# DIG_PDU.net
KiCad netlist of a schematic drawn in Altium Designer
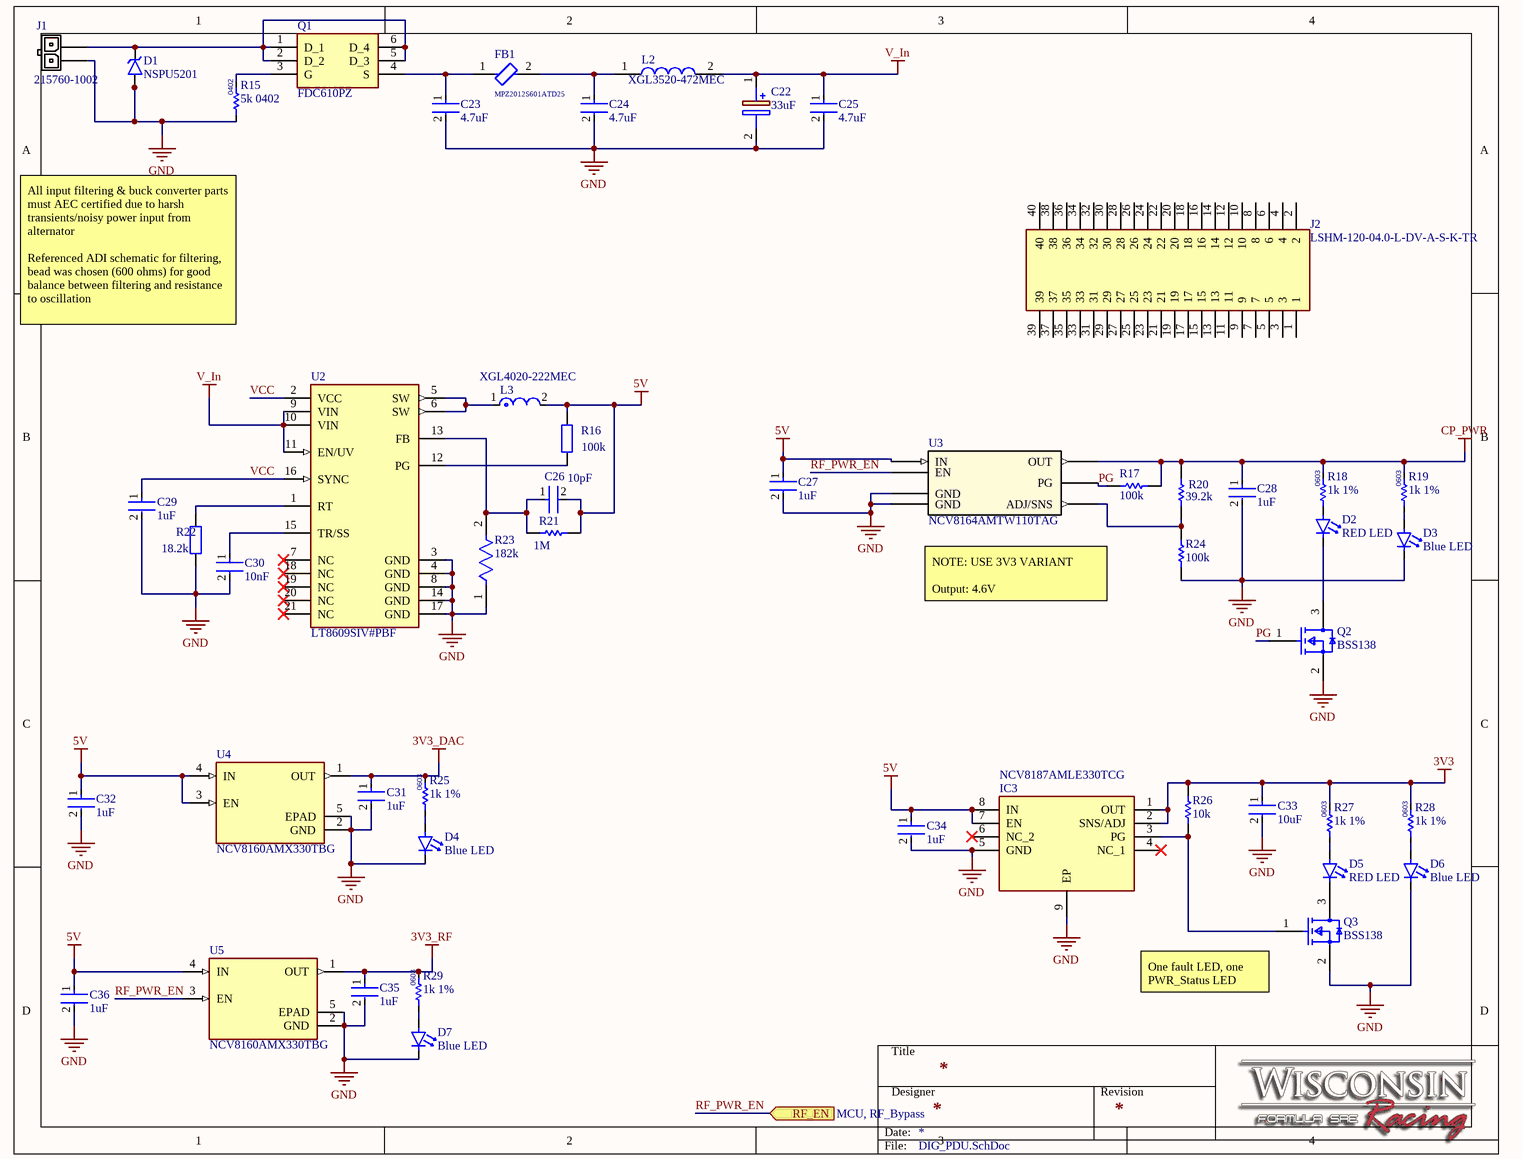
[diagram p0: DIG_PDU.SchDoc]

(export (version "E")
  (design (tool "Eeschema 10.0.6"))
  (components
    (comp (ref "C22")
      (value "33uF")
      (footprint "SamacSys:MAL215097904E3")
      (description "Capacitor Polarised\r\n\r\nMAL215097904E3")
      (fields
        (field (name "MANUFACTURER_PART_NUMBER") "MAL215097904E3")
        (field (name "MOUSER PART NUMBER") "594-MAL215097904E3")
      )
      (libsource (lib "*") (part "MAL215097904E3"))
    )
    (comp (ref "C23")
      (value "4.7uF")
      (footprint "FP-CGA4J-IPC_C")
      (description "Cap Ceramic 4.7uF 50V X7R 10% Pad SMD 0805 +125°C Automotive T/R")
      (libsource (lib "Altium Content Vault") (part "b4654b650e69147ec39a6b967a45e02"))
    )
    (comp (ref "C24")
      (value "4.7uF")
      (footprint "FP-CGA4J-IPC_C")
      (description "Cap Ceramic 4.7uF 50V X7R 10% Pad SMD 0805 +125°C Automotive T/R")
      (libsource (lib "Altium Content Vault") (part "b4654b650e69147ec39a6b967a45e02"))
    )
    (comp (ref "C25")
      (value "4.7uF")
      (footprint "FP-CGA4J-IPC_C")
      (description "Cap Ceramic 4.7uF 50V X7R 10% Pad SMD 0805 +125°C Automotive T/R")
      (libsource (lib "Altium Content Vault") (part "b4654b650e69147ec39a6b967a45e02"))
    )
    (comp (ref "C26")
      (value "10pF")
      (footprint "FP-GCM155-0_05-IPC_C")
      (description "Ceramic Capacitor for Automotive 10pF ±5% 50VDC C0G 0402 Paper T/R")
      (fields (field (name "TOLERANCE") "5%"))
      (libsource (lib "Altium Content Vault") (part "02cd4be3c70576c341d710602a673aa"))
    )
    (comp (ref "C27")
      (value "1uF")
      (footprint "FP-GRM155-0_1-IPC_C")
      (libsource (lib "Altium Content Vault") (part "11868f565c42a9108669ba33697ecf6"))
    )
    (comp (ref "C28")
      (value "1uF")
      (footprint "FP-GRM155-0_1-IPC_C")
      (libsource (lib "Altium Content Vault") (part "11868f565c42a9108669ba33697ecf6"))
    )
    (comp (ref "C29")
      (value "1uF")
      (footprint "FP-GRT155-0_1-IPC_A")
      (description "Multi-Layer Ceramic Capacitor 1uF 25V X6S ±10% 0402 Paper T/R\r\n\r\nGRT155C81E105KE13D")
      (libsource (lib "Altium Content Vault") (part "02cd4be3c70576c341d710602a673aa"))
    )
    (comp (ref "C30")
      (value "10nF")
      (footprint "FP-GCM155-0_05-IPC_C")
      (description "Ceramic Capacitor for Automotive 10nF ±10% 50VDC X7R 0402 Paper T/R\r\n\r\nGCM155R71H103KA55D")
      (fields (field (name "TOLERANCE") "10%") (field (name "VOLTAGE") "50V"))
      (libsource (lib "Altium Content Vault") (part "02cd4be3c70576c341d710602a673aa"))
    )
    (comp (ref "C31")
      (value "1uF")
      (footprint "FP-GRM155-0_1-IPC_C")
      (libsource (lib "Altium Content Vault") (part "11868f565c42a9108669ba33697ecf6"))
    )
    (comp (ref "C32")
      (value "1uF")
      (footprint "FP-GRM155-0_1-IPC_C")
      (libsource (lib "Altium Content Vault") (part "11868f565c42a9108669ba33697ecf6"))
    )
    (comp (ref "C33")
      (value "10uF")
      (footprint "FP-GRM155-0_2-IPC_A")
      (description "Chip Multilayer Ceramic Capacitors for General Purpose, 0402, 10uF, X5R, 15%, 20%, 6.3V")
      (libsource (lib "Altium Content Vault") (part "b4654b650e69147ec39a6b967a45e02"))
    )
    (comp (ref "C34")
      (value "1uF")
      (footprint "FP-GRM155-0_1-IPC_C")
      (libsource (lib "Altium Content Vault") (part "11868f565c42a9108669ba33697ecf6"))
    )
    (comp (ref "C35")
      (value "1uF")
      (footprint "FP-GRM155-0_1-IPC_C")
      (libsource (lib "Altium Content Vault") (part "11868f565c42a9108669ba33697ecf6"))
    )
    (comp (ref "C36")
      (value "1uF")
      (footprint "FP-GRM155-0_1-IPC_C")
      (libsource (lib "Altium Content Vault") (part "11868f565c42a9108669ba33697ecf6"))
    )
    (comp (ref "D1")
      (value "NSPU5201")
      (footprint "NSPM5131MUTBG")
      (fields
        (field (name "ARROW PART NUMBER") "NSPU5201MUTBG")
        (field (name "MOUSER PART NUMBER") "863-NSPU5201MUTBG")
      )
      (libsource (lib "University of Wisconsin Formula FSAE") (part "NSPU5201MUTBG"))
    )
    (comp (ref "D2")
      (value "RED LED")
      (footprint "DIOC1608X05N")
      (description "0603 Red SMD Led")
      (libsource (lib "University of Wisconsin Formula FSAE") (part "L196L-LIC-Symbol-1"))
    )
    (comp (ref "D3")
      (value "Blue LED")
      (footprint "0603-LED-1")
      (description "Single Color LED, Blue, Water Clear, 1.1mm")
      (libsource (lib "University of Wisconsin Formula FSAE") (part "LED"))
    )
    (comp (ref "D4")
      (value "Blue LED")
      (footprint "0603-LED-1")
      (description "Single Color LED, Blue, Water Clear, 1.1mm")
      (libsource (lib "University of Wisconsin Formula FSAE") (part "LED"))
    )
    (comp (ref "D5")
      (value "RED LED")
      (footprint "DIOC1608X05N")
      (description "0603 Red SMD Led")
      (libsource (lib "University of Wisconsin Formula FSAE") (part "L196L-LIC-Symbol-1"))
    )
    (comp (ref "D6")
      (value "Blue LED")
      (footprint "0603-LED-1")
      (description "Single Color LED, Blue, Water Clear, 1.1mm")
      (libsource (lib "University of Wisconsin Formula FSAE") (part "LED"))
    )
    (comp (ref "D7")
      (value "Blue LED")
      (footprint "0603-LED-1")
      (description "Single Color LED, Blue, Water Clear, 1.1mm")
      (libsource (lib "University of Wisconsin Formula FSAE") (part "LED"))
    )
    (comp (ref "FB1")
      (value "MPZ2012S601ATD25")
      (footprint "BEADC2012X105N")
      (description "Ferrite Beads Multi-Layer Power 600Ohm 25% 100MHz 2A 100mOhm DCR 0805 Automotive T/R")
      (fields (field (name "MOUSER PART NUMBER") "810-MPZ2012S601ATD25"))
      (libsource (lib "University of Wisconsin Formula FSAE") (part "MPZ2012S601ATD25"))
    )
    (comp (ref "IC3")
      (value "NCV8187AMLE330TCG")
      (footprint "SamacSys:SON65P300X300X100-9N-D")
      (description "Integrated Circuit")
      (fields (field (name "MOUSER PART NUMBER") "863-CV8187AMLE330TCG"))
      (libsource (lib "*") (part "NCV8187AMLE330TCG"))
    )
    (comp (ref "J1")
      (value "215760-1002")
      (footprint "215760-1002-Footprint-1")
      (libsource (lib "University of Wisconsin Formula FSAE") (part "961102-6404-AR"))
    )
    (comp (ref "J2")
      (value "LSHM-120-04.0-L-DV-A-S-K-TR")
      (footprint "SamacSys:LSHM-120-XX.X-YYY-DV-A-S-K-TR")
      (description "Connector")
      (fields (field (name "MOUSER PART NUMBER") "200-LSHM12004LDVASK"))
      (libsource (lib "*") (part "LSHM-120-04.0-L-DV-A-S-K-TR"))
    )
    (comp (ref "L2")
      (value "XGL3520-472MEC")
      (footprint "SamacSys:XGL3520472MEC")
      (description "Inductor")
      (libsource (lib "*") (part "XGL3520-472MEC"))
    )
    (comp (ref "L3")
      (value "XGL4020-222MEC")
      (footprint "FP-XGL4020-MFG")
      (description "Shielded Power Inductors")
      (libsource (lib "Altium Content Vault") (part "4cc4b267dca4c8e51f7102f422741d8"))
    )
    (comp (ref "Q1")
      (value "FDC610PZ")
      (footprint "SamacSys:SOT95P280X110-6N")
      (description "MOSFET (P-Channel)")
      (fields (field (name "MOUSER PART NUMBER") "512-FDC610PZ"))
      (libsource (lib "*") (part "FDC610PZ"))
    )
    (comp (ref "Q2")
      (value "BSS138")
      (footprint "FP-318-08-IPC_B")
      (description "MOSFET N-CH 50V 220MA SOT-23")
      (libsource (lib "Altium Content Vault") (part "3b9c635fedb024a5347a57b145af9cc"))
    )
    (comp (ref "Q3")
      (value "BSS138")
      (footprint "FP-318-08-IPC_B")
      (description "MOSFET N-CH 50V 220MA SOT-23")
      (libsource (lib "Altium Content Vault") (part "3b9c635fedb024a5347a57b145af9cc"))
    )
    (comp (ref "R15")
      (value "5k 0402")
      (footprint "Res0402-Type-1")
      (fields (field (name "TOLERANCE") "1%") (field (name "POWER") "63mW"))
      (libsource (lib "University of Wisconsin Formula FSAE") (part "RES"))
    )
    (comp (ref "R16")
      (value "100k")
      (footprint "WRIS-RSKS_0402")
      (description "Resistor, 100K, 0.1W, Thick Film, 0402 Rohs Compliant: Yes")
      (libsource (lib "Altium Content Vault") (part "Resistor"))
    )
    (comp (ref "R17")
      (value "100k")
      (footprint "RESC1005X40X25NL05T10")
      (fields (field (name "PART NUMBER") "RC0402FR-07100KL") (field (name "MANUFACTURER") "Yageo / Phycomp"))
      (libsource (lib "Altium Content Vault") (part "RES"))
    )
    (comp (ref "R18")
      (value "1k 1%")
      (footprint "Res0603-type-1")
      (libsource (lib "University of Wisconsin Formula FSAE") (part "RES 0603"))
    )
    (comp (ref "R19")
      (value "1k 1%")
      (footprint "Res0603-type-1")
      (libsource (lib "University of Wisconsin Formula FSAE") (part "RES 0603"))
    )
    (comp (ref "R20")
      (value "39.2k")
      (footprint "RESC1005X40X25ML05T10")
      (fields (field (name "PART NUMBER") "RC0402FR-0739K2L") (field (name "MANUFACTURER") "Yageo"))
      (libsource (lib "Altium Content Vault") (part "RES"))
    )
    (comp (ref "R21")
      (value "1M")
      (footprint "RESC1005X40X25NL05T10")
      (fields (field (name "MANUFACTURER") "Yageo / Phycomp") (field (name "PART NUMBER") "RC0402FR-071ML"))
      (libsource (lib "Altium Content Vault") (part "RES"))
    )
    (comp (ref "R22")
      (value "18.2k")
      (footprint "WRIS-RSKS_0402")
      (description "Resistor, 18K2, 0.1W, Thick Film, 0402 Rohs Compliant: Yes")
      (libsource (lib "Altium Content Vault") (part "Resistor"))
    )
    (comp (ref "R23")
      (value "182k")
      (footprint "FP-AC0402-IPC_C")
      (description "RES 182kΩ ±1% 0.063W 0402")
      (fields (field (name "TOLERANCE") "1%"))
      (libsource (lib "Altium Content Vault") (part "1029c3af85768c4190bb7ad29bc67b5"))
    )
    (comp (ref "R24")
      (value "100k")
      (footprint "RESC1005X40X25NL05T10")
      (fields (field (name "PART NUMBER") "RC0402FR-07100KL") (field (name "MANUFACTURER") "Yageo / Phycomp"))
      (libsource (lib "Altium Content Vault") (part "RES"))
    )
    (comp (ref "R25")
      (value "1k 1%")
      (footprint "Res0603-type-1")
      (libsource (lib "University of Wisconsin Formula FSAE") (part "RES 0603"))
    )
    (comp (ref "R26")
      (value "10k")
      (footprint "RESC1005X40X25ML05T05")
      (fields (field (name "PART NUMBER") "ERJ-2GEJ103X") (field (name "MANUFACTURER") "Panasonic"))
      (libsource (lib "Altium Content Vault") (part "RES"))
    )
    (comp (ref "R27")
      (value "1k 1%")
      (footprint "Res0603-type-1")
      (libsource (lib "University of Wisconsin Formula FSAE") (part "RES 0603"))
    )
    (comp (ref "R28")
      (value "1k 1%")
      (footprint "Res0603-type-1")
      (libsource (lib "University of Wisconsin Formula FSAE") (part "RES 0603"))
    )
    (comp (ref "R29")
      (value "1k 1%")
      (footprint "Res0603-type-1")
      (libsource (lib "University of Wisconsin Formula FSAE") (part "RES 0603"))
    )
    (comp (ref "U2")
      (value "LT8609SIV#PBF")
      (footprint "FP-LQFN-16-05-08-1516-MFG")
      (description "IC REG BUCK ADJUSTABLE 2A 16LQFN")
      (fields
        (field (name "OCTOPART") "https://octopart.com/lt8609siv%23pbf-analog+devices-88316701")
        (field (name "MANUFACTURER") "Analog Devices")
      )
      (libsource (lib "Altium Content Vault") (part "5cdaaed650003e075ab076d5d3b68d5"))
    )
    (comp (ref "U3")
      (value "NCV8164AMTW110TAG")
      (footprint "WDFNW6_511DW_OSI")
      (description "LDO")
      (fields (field (name "COPYRIGHT") "Copyright (C) 2025 Ultra Librarian. All rights reserved."))
      (libsource (lib "University of Wisconsin Formula FSAE") (part "NCV8164AMTW110TAG"))
    )
    (comp (ref "U4")
      (value "NCV8160AMX330TBG")
      (footprint "VREG_NCV8160AMX330TBG")
      (description "Linear Voltage Regulator IC Positive Fixed 1 Output 250mA 4-XDFN (1x1)")
      (fields (field (name "MF") "ON Semiconductor"))
      (libsource (lib "University of Wisconsin Formula FSAE") (part "NCV8160AMX330TBG"))
    )
    (comp (ref "U5")
      (value "NCV8160AMX330TBG")
      (footprint "VREG_NCV8160AMX330TBG")
      (description "Linear Voltage Regulator IC Positive Fixed 1 Output 250mA 4-XDFN (1x1)")
      (fields (field (name "MF") "ON Semiconductor"))
      (libsource (lib "University of Wisconsin Formula FSAE") (part "NCV8160AMX330TBG"))
    )
  )
  (nets
    (net (code "1") (name "/PG") (class "Default")
      (node (ref "Q2") (pin "1") (pinfunction "G_1") (pintype "passive"))
      (node (ref "R17") (pin "2") (pinfunction "2_2") (pintype "passive"))
      (node (ref "U3") (pin "3") (pinfunction "PG_3") (pintype "passive"))
    )
    (net (code "2") (name "/RF_PWR_EN") (class "Default")
      (node (ref "U3") (pin "4") (pinfunction "EN_4") (pintype "passive"))
      (node (ref "U5") (pin "3") (pinfunction "EN_3") (pintype "input"))
    )
    (net (code "3") (name "/VCC") (class "Default")
      (node (ref "C29") (pin "1") (pinfunction "1_1") (pintype "passive"))
      (node (ref "U2") (pin "16") (pinfunction "SYNC_16") (pintype "input"))
      (node (ref "U2") (pin "2") (pinfunction "VCC_2") (pintype "power_in"))
    )
    (net (code "4") (name "3V3") (class "Default")
      (node (ref "C33") (pin "1") (pinfunction "1_1") (pintype "passive"))
      (node (ref "IC3") (pin "1") (pinfunction "OUT_1") (pintype "passive"))
      (node (ref "IC3") (pin "2") (pinfunction "SNS/ADJ_2") (pintype "passive"))
      (node (ref "R26") (pin "2") (pinfunction "2_2") (pintype "passive"))
      (node (ref "R27") (pin "2") (pinfunction "2_2") (pintype "passive"))
      (node (ref "R28") (pin "2") (pinfunction "2_2") (pintype "passive"))
    )
    (net (code "5") (name "3V3_DAC") (class "Default")
      (node (ref "C31") (pin "1") (pinfunction "1_1") (pintype "passive"))
      (node (ref "R25") (pin "2") (pinfunction "2_2") (pintype "passive"))
      (node (ref "U4") (pin "1") (pinfunction "OUT_1") (pintype "output"))
    )
    (net (code "6") (name "3V3_RF") (class "Default")
      (node (ref "C35") (pin "1") (pinfunction "1_1") (pintype "passive"))
      (node (ref "R29") (pin "2") (pinfunction "2_2") (pintype "passive"))
      (node (ref "U5") (pin "1") (pinfunction "OUT_1") (pintype "output"))
    )
    (net (code "7") (name "5V") (class "Default")
      (node (ref "C26") (pin "2") (pinfunction "2_2") (pintype "passive"))
      (node (ref "C27") (pin "1") (pinfunction "1_1") (pintype "passive"))
      (node (ref "C32") (pin "1") (pinfunction "1_1") (pintype "passive"))
      (node (ref "C34") (pin "1") (pinfunction "1_1") (pintype "passive"))
      (node (ref "C36") (pin "1") (pinfunction "1_1") (pintype "passive"))
      (node (ref "IC3") (pin "7") (pinfunction "EN_7") (pintype "passive"))
      (node (ref "IC3") (pin "8") (pinfunction "IN_8") (pintype "passive"))
      (node (ref "L3") (pin "2") (pinfunction "2_2") (pintype "passive"))
      (node (ref "R16") (pin "2") (pinfunction "2_2") (pintype "passive"))
      (node (ref "R21") (pin "2") (pinfunction "2_2") (pintype "passive"))
      (node (ref "U3") (pin "6") (pinfunction "IN_6") (pintype "input"))
      (node (ref "U4") (pin "3") (pinfunction "EN_3") (pintype "input"))
      (node (ref "U4") (pin "4") (pinfunction "IN_4") (pintype "input"))
      (node (ref "U5") (pin "4") (pinfunction "IN_4") (pintype "input"))
    )
    (net (code "8") (name "CP_PWR") (class "Default")
      (node (ref "C28") (pin "1") (pinfunction "1_1") (pintype "passive"))
      (node (ref "R17") (pin "1") (pinfunction "1_1") (pintype "passive"))
      (node (ref "R18") (pin "2") (pinfunction "2_2") (pintype "passive"))
      (node (ref "R19") (pin "2") (pinfunction "2_2") (pintype "passive"))
      (node (ref "R20") (pin "2") (pinfunction "2_2") (pintype "passive"))
      (node (ref "U3") (pin "1") (pinfunction "OUT_1") (pintype "output"))
    )
    (net (code "9") (name "GND") (class "Default")
      (node (ref "C22") (pin "2") (pinfunction "-_2") (pintype "passive"))
      (node (ref "C23") (pin "2") (pinfunction "2_2") (pintype "passive"))
      (node (ref "C24") (pin "2") (pinfunction "2_2") (pintype "passive"))
      (node (ref "C25") (pin "2") (pinfunction "2_2") (pintype "passive"))
      (node (ref "C27") (pin "2") (pinfunction "2_2") (pintype "passive"))
      (node (ref "C28") (pin "2") (pinfunction "2_2") (pintype "passive"))
      (node (ref "C29") (pin "2") (pinfunction "2_2") (pintype "passive"))
      (node (ref "C30") (pin "2") (pinfunction "2_2") (pintype "passive"))
      (node (ref "C31") (pin "2") (pinfunction "2_2") (pintype "passive"))
      (node (ref "C32") (pin "2") (pinfunction "2_2") (pintype "passive"))
      (node (ref "C33") (pin "2") (pinfunction "2_2") (pintype "passive"))
      (node (ref "C34") (pin "2") (pinfunction "2_2") (pintype "passive"))
      (node (ref "C35") (pin "2") (pinfunction "2_2") (pintype "passive"))
      (node (ref "C36") (pin "2") (pinfunction "2_2") (pintype "passive"))
      (node (ref "D1") (pin "5") (pinfunction "GND_(A)_1_5") (pintype "passive"))
      (node (ref "D1") (pin "6") (pinfunction "GND_(A)_2_6") (pintype "passive"))
      (node (ref "D1") (pin "7") (pinfunction "GND_(A)_3_7") (pintype "passive"))
      (node (ref "D1") (pin "8") (pinfunction "GND_(A)_4_8") (pintype "passive"))
      (node (ref "D3") (pin "1") (pinfunction "C_1") (pintype "passive"))
      (node (ref "D4") (pin "1") (pinfunction "C_1") (pintype "passive"))
      (node (ref "D6") (pin "1") (pinfunction "C_1") (pintype "passive"))
      (node (ref "D7") (pin "1") (pinfunction "C_1") (pintype "passive"))
      (node (ref "IC3") (pin "5") (pinfunction "GND_5") (pintype "passive"))
      (node (ref "IC3") (pin "9") (pinfunction "EP_9") (pintype "passive"))
      (node (ref "J1") (pin "2") (pinfunction "2_2") (pintype "passive"))
      (node (ref "Q2") (pin "2") (pinfunction "S_2") (pintype "passive"))
      (node (ref "Q3") (pin "2") (pinfunction "S_2") (pintype "passive"))
      (node (ref "R15") (pin "1") (pinfunction "1_1") (pintype "passive"))
      (node (ref "R22") (pin "1") (pinfunction "1_1") (pintype "passive"))
      (node (ref "R23") (pin "1") (pinfunction "1_1") (pintype "passive"))
      (node (ref "R24") (pin "1") (pinfunction "1_1") (pintype "passive"))
      (node (ref "U2") (pin "14") (pinfunction "GND_14") (pintype "power_in"))
      (node (ref "U2") (pin "17") (pinfunction "GND_17") (pintype "power_in"))
      (node (ref "U2") (pin "3") (pinfunction "GND_3") (pintype "power_in"))
      (node (ref "U2") (pin "4") (pinfunction "GND_4") (pintype "power_in"))
      (node (ref "U2") (pin "8") (pinfunction "GND_8") (pintype "power_in"))
      (node (ref "U3") (pin "5") (pinfunction "GND_5") (pintype "power_in"))
      (node (ref "U3") (pin "7") (pinfunction "GND_7") (pintype "power_in"))
      (node (ref "U4") (pin "2") (pinfunction "GND_2") (pintype "power_in"))
      (node (ref "U4") (pin "5") (pinfunction "EPAD_5") (pintype "power_in"))
      (node (ref "U5") (pin "2") (pinfunction "GND_2") (pintype "power_in"))
      (node (ref "U5") (pin "5") (pinfunction "EPAD_5") (pintype "power_in"))
    )
    (net (code "10") (name "Net-(C24-Pad1)") (class "Default")
      (node (ref "C24") (pin "1") (pinfunction "1_1") (pintype "passive"))
      (node (ref "FB1") (pin "2") (pinfunction "2_2") (pintype "passive"))
      (node (ref "L2") (pin "1") (pinfunction "1_1") (pintype "passive"))
    )
    (net (code "11") (name "Net-(D2-C)") (class "Default")
      (node (ref "D2") (pin "1") (pinfunction "C_1") (pintype "passive"))
      (node (ref "Q2") (pin "3") (pinfunction "D_3") (pintype "passive"))
    )
    (net (code "12") (name "Net-(D3-A)") (class "Default")
      (node (ref "D3") (pin "2") (pinfunction "A_2") (pintype "passive"))
      (node (ref "R19") (pin "1") (pinfunction "1_1") (pintype "passive"))
    )
    (net (code "13") (name "Net-(D4-A)") (class "Default")
      (node (ref "D4") (pin "2") (pinfunction "A_2") (pintype "passive"))
      (node (ref "R25") (pin "1") (pinfunction "1_1") (pintype "passive"))
    )
    (net (code "14") (name "Net-(D5-A)") (class "Default")
      (node (ref "D5") (pin "2") (pinfunction "A_2") (pintype "passive"))
      (node (ref "R27") (pin "1") (pinfunction "1_1") (pintype "passive"))
    )
    (net (code "15") (name "Net-(D5-C)") (class "Default")
      (node (ref "D5") (pin "1") (pinfunction "C_1") (pintype "passive"))
      (node (ref "Q3") (pin "3") (pinfunction "D_3") (pintype "passive"))
    )
    (net (code "16") (name "Net-(D6-A)") (class "Default")
      (node (ref "D6") (pin "2") (pinfunction "A_2") (pintype "passive"))
      (node (ref "R28") (pin "1") (pinfunction "1_1") (pintype "passive"))
    )
    (net (code "17") (name "Net-(D7-A)") (class "Default")
      (node (ref "D7") (pin "2") (pinfunction "A_2") (pintype "passive"))
      (node (ref "R29") (pin "1") (pinfunction "1_1") (pintype "passive"))
    )
    (net (code "18") (name "Net-(IC3-PG)") (class "Default")
      (node (ref "IC3") (pin "3") (pinfunction "PG_3") (pintype "passive"))
      (node (ref "Q3") (pin "1") (pinfunction "G_1") (pintype "passive"))
      (node (ref "R26") (pin "1") (pinfunction "1_1") (pintype "passive"))
    )
    (net (code "19") (name "Net-(L3-Pad1)") (class "Default")
      (node (ref "L3") (pin "1") (pinfunction "1_1") (pintype "passive"))
      (node (ref "U2") (pin "5") (pinfunction "SW_5") (pintype "output"))
      (node (ref "U2") (pin "6") (pinfunction "SW_6") (pintype "output"))
    )
    (net (code "20") (name "Net-(Q1-D_1)") (class "Default")
      (node (ref "D1") (pin "1") (pinfunction "1_1") (pintype "passive"))
      (node (ref "D1") (pin "2") (pinfunction "2_2") (pintype "passive"))
      (node (ref "J1") (pin "1") (pinfunction "1_1") (pintype "passive"))
      (node (ref "Q1") (pin "1") (pinfunction "D_1_1") (pintype "passive"))
      (node (ref "Q1") (pin "2") (pinfunction "D_2_2") (pintype "passive"))
      (node (ref "Q1") (pin "5") (pinfunction "D_3_5") (pintype "passive"))
      (node (ref "Q1") (pin "6") (pinfunction "D_4_6") (pintype "passive"))
    )
    (net (code "21") (name "Net-(Q1-G)") (class "Default")
      (node (ref "Q1") (pin "3") (pinfunction "G_3") (pintype "passive"))
      (node (ref "R15") (pin "2") (pinfunction "2_2") (pintype "passive"))
    )
    (net (code "22") (name "Net-(Q1-S)") (class "Default")
      (node (ref "C23") (pin "1") (pinfunction "1_1") (pintype "passive"))
      (node (ref "FB1") (pin "1") (pinfunction "1_1") (pintype "passive"))
      (node (ref "Q1") (pin "4") (pinfunction "S_4") (pintype "passive"))
    )
    (net (code "23") (name "Net-(U2-FB)") (class "Default")
      (node (ref "C26") (pin "1") (pinfunction "1_1") (pintype "passive"))
      (node (ref "R21") (pin "1") (pinfunction "1_1") (pintype "passive"))
      (node (ref "R23") (pin "2") (pinfunction "2_2") (pintype "passive"))
      (node (ref "U2") (pin "13") (pinfunction "FB_13") (pintype "passive"))
    )
    (net (code "24") (name "Net-(U2-PG)") (class "Default")
      (node (ref "R16") (pin "1") (pinfunction "1_1") (pintype "passive"))
      (node (ref "U2") (pin "12") (pinfunction "PG_12") (pintype "open_collector"))
    )
    (net (code "25") (name "Net-(U2-RT)") (class "Default")
      (node (ref "R22") (pin "2") (pinfunction "2_2") (pintype "passive"))
      (node (ref "U2") (pin "1") (pinfunction "RT_1") (pintype "passive"))
    )
    (net (code "26") (name "Net-(U2-TR{slash}SS)") (class "Default")
      (node (ref "C30") (pin "1") (pinfunction "1_1") (pintype "passive"))
      (node (ref "U2") (pin "15") (pinfunction "TR/SS_15") (pintype "passive"))
    )
    (net (code "27") (name "Net-(U3-ADJ{slash}SNS)") (class "Default")
      (node (ref "R20") (pin "1") (pinfunction "1_1") (pintype "passive"))
      (node (ref "R24") (pin "2") (pinfunction "2_2") (pintype "passive"))
      (node (ref "U3") (pin "2") (pinfunction "ADJ/SNS_2") (pintype "output"))
    )
    (net (code "28") (name "V_In") (class "Default")
      (node (ref "C22") (pin "1") (pinfunction "+_1") (pintype "passive"))
      (node (ref "C25") (pin "1") (pinfunction "1_1") (pintype "passive"))
      (node (ref "L2") (pin "2") (pinfunction "2_2") (pintype "passive"))
      (node (ref "U2") (pin "10") (pinfunction "VIN_10") (pintype "power_in"))
      (node (ref "U2") (pin "11") (pinfunction "EN/UV_11") (pintype "input"))
      (node (ref "U2") (pin "9") (pinfunction "VIN_9") (pintype "power_in"))
    )
    (net (code "29") (name "unconnected-(D2-A-Pad2)") (class "Default")
      (node (ref "D2") (pin "2") (pinfunction "A_2") (pintype "passive"))
    )
    (net (code "30") (name "unconnected-(IC3-NC_1-Pad4)") (class "Default")
      (node (ref "IC3") (pin "4") (pinfunction "NC_1_4") (pintype "passive+no_connect"))
    )
    (net (code "31") (name "unconnected-(IC3-NC_2-Pad6)") (class "Default")
      (node (ref "IC3") (pin "6") (pinfunction "NC_2_6") (pintype "passive+no_connect"))
    )
    (net (code "32") (name "unconnected-(J2-Pad1)") (class "Default")
      (node (ref "J2") (pin "1") (pinfunction "1_1") (pintype "passive"))
    )
    (net (code "33") (name "unconnected-(J2-Pad2)") (class "Default")
      (node (ref "J2") (pin "2") (pinfunction "2_2") (pintype "passive"))
    )
    (net (code "34") (name "unconnected-(J2-Pad3)") (class "Default")
      (node (ref "J2") (pin "3") (pinfunction "3_3") (pintype "passive"))
    )
    (net (code "35") (name "unconnected-(J2-Pad4)") (class "Default")
      (node (ref "J2") (pin "4") (pinfunction "4_4") (pintype "passive"))
    )
    (net (code "36") (name "unconnected-(J2-Pad5)") (class "Default")
      (node (ref "J2") (pin "5") (pinfunction "5_5") (pintype "passive"))
    )
    (net (code "37") (name "unconnected-(J2-Pad6)") (class "Default")
      (node (ref "J2") (pin "6") (pinfunction "6_6") (pintype "passive"))
    )
    (net (code "38") (name "unconnected-(J2-Pad7)") (class "Default")
      (node (ref "J2") (pin "7") (pinfunction "7_7") (pintype "passive"))
    )
    (net (code "39") (name "unconnected-(J2-Pad8)") (class "Default")
      (node (ref "J2") (pin "8") (pinfunction "8_8") (pintype "passive"))
    )
    (net (code "40") (name "unconnected-(J2-Pad9)") (class "Default")
      (node (ref "J2") (pin "9") (pinfunction "9_9") (pintype "passive"))
    )
    (net (code "41") (name "unconnected-(J2-Pad10)") (class "Default")
      (node (ref "J2") (pin "10") (pinfunction "10_10") (pintype "passive"))
    )
    (net (code "42") (name "unconnected-(J2-Pad11)") (class "Default")
      (node (ref "J2") (pin "11") (pinfunction "11_11") (pintype "passive"))
    )
    (net (code "43") (name "unconnected-(J2-Pad12)") (class "Default")
      (node (ref "J2") (pin "12") (pinfunction "12_12") (pintype "passive"))
    )
    (net (code "44") (name "unconnected-(J2-Pad13)") (class "Default")
      (node (ref "J2") (pin "13") (pinfunction "13_13") (pintype "passive"))
    )
    (net (code "45") (name "unconnected-(J2-Pad14)") (class "Default")
      (node (ref "J2") (pin "14") (pinfunction "14_14") (pintype "passive"))
    )
    (net (code "46") (name "unconnected-(J2-Pad15)") (class "Default")
      (node (ref "J2") (pin "15") (pinfunction "15_15") (pintype "passive"))
    )
    (net (code "47") (name "unconnected-(J2-Pad16)") (class "Default")
      (node (ref "J2") (pin "16") (pinfunction "16_16") (pintype "passive"))
    )
    (net (code "48") (name "unconnected-(J2-Pad17)") (class "Default")
      (node (ref "J2") (pin "17") (pinfunction "17_17") (pintype "passive"))
    )
    (net (code "49") (name "unconnected-(J2-Pad18)") (class "Default")
      (node (ref "J2") (pin "18") (pinfunction "18_18") (pintype "passive"))
    )
    (net (code "50") (name "unconnected-(J2-Pad19)") (class "Default")
      (node (ref "J2") (pin "19") (pinfunction "19_19") (pintype "passive"))
    )
    (net (code "51") (name "unconnected-(J2-Pad20)") (class "Default")
      (node (ref "J2") (pin "20") (pinfunction "20_20") (pintype "passive"))
    )
    (net (code "52") (name "unconnected-(J2-Pad21)") (class "Default")
      (node (ref "J2") (pin "21") (pinfunction "21_21") (pintype "passive"))
    )
    (net (code "53") (name "unconnected-(J2-Pad22)") (class "Default")
      (node (ref "J2") (pin "22") (pinfunction "22_22") (pintype "passive"))
    )
    (net (code "54") (name "unconnected-(J2-Pad23)") (class "Default")
      (node (ref "J2") (pin "23") (pinfunction "23_23") (pintype "passive"))
    )
    (net (code "55") (name "unconnected-(J2-Pad24)") (class "Default")
      (node (ref "J2") (pin "24") (pinfunction "24_24") (pintype "passive"))
    )
    (net (code "56") (name "unconnected-(J2-Pad25)") (class "Default")
      (node (ref "J2") (pin "25") (pinfunction "25_25") (pintype "passive"))
    )
    (net (code "57") (name "unconnected-(J2-Pad26)") (class "Default")
      (node (ref "J2") (pin "26") (pinfunction "26_26") (pintype "passive"))
    )
    (net (code "58") (name "unconnected-(J2-Pad27)") (class "Default")
      (node (ref "J2") (pin "27") (pinfunction "27_27") (pintype "passive"))
    )
    (net (code "59") (name "unconnected-(J2-Pad28)") (class "Default")
      (node (ref "J2") (pin "28") (pinfunction "28_28") (pintype "passive"))
    )
    (net (code "60") (name "unconnected-(J2-Pad29)") (class "Default")
      (node (ref "J2") (pin "29") (pinfunction "29_29") (pintype "passive"))
    )
    (net (code "61") (name "unconnected-(J2-Pad30)") (class "Default")
      (node (ref "J2") (pin "30") (pinfunction "30_30") (pintype "passive"))
    )
    (net (code "62") (name "unconnected-(J2-Pad31)") (class "Default")
      (node (ref "J2") (pin "31") (pinfunction "31_31") (pintype "passive"))
    )
    (net (code "63") (name "unconnected-(J2-Pad32)") (class "Default")
      (node (ref "J2") (pin "32") (pinfunction "32_32") (pintype "passive"))
    )
    (net (code "64") (name "unconnected-(J2-Pad33)") (class "Default")
      (node (ref "J2") (pin "33") (pinfunction "33_33") (pintype "passive"))
    )
    (net (code "65") (name "unconnected-(J2-Pad34)") (class "Default")
      (node (ref "J2") (pin "34") (pinfunction "34_34") (pintype "passive"))
    )
    (net (code "66") (name "unconnected-(J2-Pad35)") (class "Default")
      (node (ref "J2") (pin "35") (pinfunction "35_35") (pintype "passive"))
    )
    (net (code "67") (name "unconnected-(J2-Pad36)") (class "Default")
      (node (ref "J2") (pin "36") (pinfunction "36_36") (pintype "passive"))
    )
    (net (code "68") (name "unconnected-(J2-Pad37)") (class "Default")
      (node (ref "J2") (pin "37") (pinfunction "37_37") (pintype "passive"))
    )
    (net (code "69") (name "unconnected-(J2-Pad38)") (class "Default")
      (node (ref "J2") (pin "38") (pinfunction "38_38") (pintype "passive"))
    )
    (net (code "70") (name "unconnected-(J2-Pad39)") (class "Default")
      (node (ref "J2") (pin "39") (pinfunction "39_39") (pintype "passive"))
    )
    (net (code "71") (name "unconnected-(J2-Pad40)") (class "Default")
      (node (ref "J2") (pin "40") (pinfunction "40_40") (pintype "passive"))
    )
    (net (code "72") (name "unconnected-(R18-Pad1)") (class "Default")
      (node (ref "R18") (pin "1") (pinfunction "1_1") (pintype "passive"))
    )
    (net (code "73") (name "unconnected-(U2-NC-Pad7)") (class "Default")
      (node (ref "U2") (pin "7") (pinfunction "NC_7") (pintype "passive+no_connect"))
    )
    (net (code "74") (name "unconnected-(U2-NC-Pad18)") (class "Default")
      (node (ref "U2") (pin "18") (pinfunction "NC_18") (pintype "passive+no_connect"))
    )
    (net (code "75") (name "unconnected-(U2-NC-Pad19)") (class "Default")
      (node (ref "U2") (pin "19") (pinfunction "NC_19") (pintype "passive+no_connect"))
    )
    (net (code "76") (name "unconnected-(U2-NC-Pad20)") (class "Default")
      (node (ref "U2") (pin "20") (pinfunction "NC_20") (pintype "passive+no_connect"))
    )
    (net (code "77") (name "unconnected-(U2-NC-Pad21)") (class "Default")
      (node (ref "U2") (pin "21") (pinfunction "NC_21") (pintype "passive+no_connect"))
    )
  )
)
